# so28.net
KiCad netlist of a schematic drawn in EAGLE
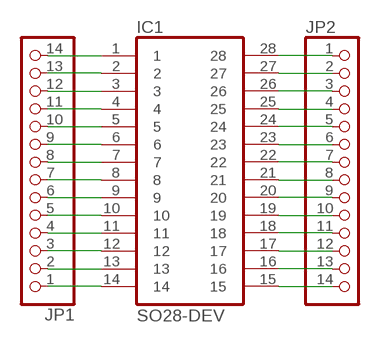
[diagram p0: schematic, sheet 1]

(export (version "E")
  (design (tool "Eeschema 10.0.6"))
  (components
    (comp (ref "IC1")
      (value "SO28-DEV")
      (footprint "eagle-import:SO28W")
      (libsource (lib "eagle-import") (part "SO28-DEV"))
    )
    (comp (ref "JP1")
      (value "PINHD-1X14")
      (footprint "eagle-import:1X14")
      (libsource (lib "eagle-import") (part "PINHD-1X14"))
    )
    (comp (ref "JP2")
      (value "PINHD-1X14")
      (footprint "eagle-import:1X14")
      (libsource (lib "eagle-import") (part "PINHD-1X14"))
    )
  )
  (nets
    (net (code "1") (name "Net-(IC1-Pad1)") (class "Default")
      (node (ref "IC1") (pin "1") (pinfunction "1_1") (pintype "bidirectional"))
      (node (ref "JP1") (pin "14") (pinfunction "14_14") (pintype "passive"))
    )
    (net (code "2") (name "Net-(IC1-Pad2)") (class "Default")
      (node (ref "IC1") (pin "2") (pinfunction "2_2") (pintype "bidirectional"))
      (node (ref "JP1") (pin "13") (pinfunction "13_13") (pintype "passive"))
    )
    (net (code "3") (name "Net-(IC1-Pad3)") (class "Default")
      (node (ref "IC1") (pin "3") (pinfunction "3_3") (pintype "bidirectional"))
      (node (ref "JP1") (pin "12") (pinfunction "12_12") (pintype "passive"))
    )
    (net (code "4") (name "Net-(IC1-Pad4)") (class "Default")
      (node (ref "IC1") (pin "4") (pinfunction "4_4") (pintype "bidirectional"))
      (node (ref "JP1") (pin "11") (pinfunction "11_11") (pintype "passive"))
    )
    (net (code "5") (name "Net-(IC1-Pad5)") (class "Default")
      (node (ref "IC1") (pin "5") (pinfunction "5_5") (pintype "bidirectional"))
      (node (ref "JP1") (pin "10") (pinfunction "10_10") (pintype "passive"))
    )
    (net (code "6") (name "Net-(IC1-Pad6)") (class "Default")
      (node (ref "IC1") (pin "6") (pinfunction "6_6") (pintype "bidirectional"))
      (node (ref "JP1") (pin "9") (pinfunction "9_9") (pintype "passive"))
    )
    (net (code "7") (name "Net-(IC1-Pad7)") (class "Default")
      (node (ref "IC1") (pin "7") (pinfunction "7_7") (pintype "bidirectional"))
      (node (ref "JP1") (pin "8") (pinfunction "8_8") (pintype "passive"))
    )
    (net (code "8") (name "Net-(IC1-Pad8)") (class "Default")
      (node (ref "IC1") (pin "8") (pinfunction "8_8") (pintype "bidirectional"))
      (node (ref "JP1") (pin "7") (pinfunction "7_7") (pintype "passive"))
    )
    (net (code "9") (name "Net-(IC1-Pad9)") (class "Default")
      (node (ref "IC1") (pin "9") (pinfunction "9_9") (pintype "bidirectional"))
      (node (ref "JP1") (pin "6") (pinfunction "6_6") (pintype "passive"))
    )
    (net (code "10") (name "Net-(IC1-Pad10)") (class "Default")
      (node (ref "IC1") (pin "10") (pinfunction "10_10") (pintype "bidirectional"))
      (node (ref "JP1") (pin "5") (pinfunction "5_5") (pintype "passive"))
    )
    (net (code "11") (name "Net-(IC1-Pad11)") (class "Default")
      (node (ref "IC1") (pin "11") (pinfunction "11_11") (pintype "bidirectional"))
      (node (ref "JP1") (pin "4") (pinfunction "4_4") (pintype "passive"))
    )
    (net (code "12") (name "Net-(IC1-Pad12)") (class "Default")
      (node (ref "IC1") (pin "12") (pinfunction "12_12") (pintype "bidirectional"))
      (node (ref "JP1") (pin "3") (pinfunction "3_3") (pintype "passive"))
    )
    (net (code "13") (name "Net-(IC1-Pad13)") (class "Default")
      (node (ref "IC1") (pin "13") (pinfunction "13_13") (pintype "bidirectional"))
      (node (ref "JP1") (pin "2") (pinfunction "2_2") (pintype "passive"))
    )
    (net (code "14") (name "Net-(IC1-Pad14)") (class "Default")
      (node (ref "IC1") (pin "14") (pinfunction "14_14") (pintype "bidirectional"))
      (node (ref "JP1") (pin "1") (pinfunction "1_1") (pintype "passive"))
    )
    (net (code "15") (name "Net-(IC1-Pad15)") (class "Default")
      (node (ref "IC1") (pin "15") (pinfunction "15_15") (pintype "bidirectional"))
      (node (ref "JP2") (pin "14") (pinfunction "14_14") (pintype "passive"))
    )
    (net (code "16") (name "Net-(IC1-Pad16)") (class "Default")
      (node (ref "IC1") (pin "16") (pinfunction "16_16") (pintype "bidirectional"))
      (node (ref "JP2") (pin "13") (pinfunction "13_13") (pintype "passive"))
    )
    (net (code "17") (name "Net-(IC1-Pad17)") (class "Default")
      (node (ref "IC1") (pin "17") (pinfunction "17_17") (pintype "bidirectional"))
      (node (ref "JP2") (pin "12") (pinfunction "12_12") (pintype "passive"))
    )
    (net (code "18") (name "Net-(IC1-Pad18)") (class "Default")
      (node (ref "IC1") (pin "18") (pinfunction "18_18") (pintype "bidirectional"))
      (node (ref "JP2") (pin "11") (pinfunction "11_11") (pintype "passive"))
    )
    (net (code "19") (name "Net-(IC1-Pad19)") (class "Default")
      (node (ref "IC1") (pin "19") (pinfunction "19_19") (pintype "bidirectional"))
      (node (ref "JP2") (pin "10") (pinfunction "10_10") (pintype "passive"))
    )
    (net (code "20") (name "Net-(IC1-Pad20)") (class "Default")
      (node (ref "IC1") (pin "20") (pinfunction "20_20") (pintype "bidirectional"))
      (node (ref "JP2") (pin "9") (pinfunction "9_9") (pintype "passive"))
    )
    (net (code "21") (name "Net-(IC1-Pad21)") (class "Default")
      (node (ref "IC1") (pin "21") (pinfunction "21_21") (pintype "bidirectional"))
      (node (ref "JP2") (pin "8") (pinfunction "8_8") (pintype "passive"))
    )
    (net (code "22") (name "Net-(IC1-Pad22)") (class "Default")
      (node (ref "IC1") (pin "22") (pinfunction "22_22") (pintype "bidirectional"))
      (node (ref "JP2") (pin "7") (pinfunction "7_7") (pintype "passive"))
    )
    (net (code "23") (name "Net-(IC1-Pad23)") (class "Default")
      (node (ref "IC1") (pin "23") (pinfunction "23_23") (pintype "bidirectional"))
      (node (ref "JP2") (pin "6") (pinfunction "6_6") (pintype "passive"))
    )
    (net (code "24") (name "Net-(IC1-Pad24)") (class "Default")
      (node (ref "IC1") (pin "24") (pinfunction "24_24") (pintype "bidirectional"))
      (node (ref "JP2") (pin "5") (pinfunction "5_5") (pintype "passive"))
    )
    (net (code "25") (name "Net-(IC1-Pad25)") (class "Default")
      (node (ref "IC1") (pin "25") (pinfunction "25_25") (pintype "bidirectional"))
      (node (ref "JP2") (pin "4") (pinfunction "4_4") (pintype "passive"))
    )
    (net (code "26") (name "Net-(IC1-Pad26)") (class "Default")
      (node (ref "IC1") (pin "26") (pinfunction "26_26") (pintype "bidirectional"))
      (node (ref "JP2") (pin "3") (pinfunction "3_3") (pintype "passive"))
    )
    (net (code "27") (name "Net-(IC1-Pad27)") (class "Default")
      (node (ref "IC1") (pin "27") (pinfunction "27_27") (pintype "bidirectional"))
      (node (ref "JP2") (pin "2") (pinfunction "2_2") (pintype "passive"))
    )
    (net (code "28") (name "Net-(IC1-Pad28)") (class "Default")
      (node (ref "IC1") (pin "28") (pinfunction "28_28") (pintype "bidirectional"))
      (node (ref "JP2") (pin "1") (pinfunction "1_1") (pintype "passive"))
    )
  )
)
